# TinyFET.net
KiCad netlist of a schematic drawn in EAGLE
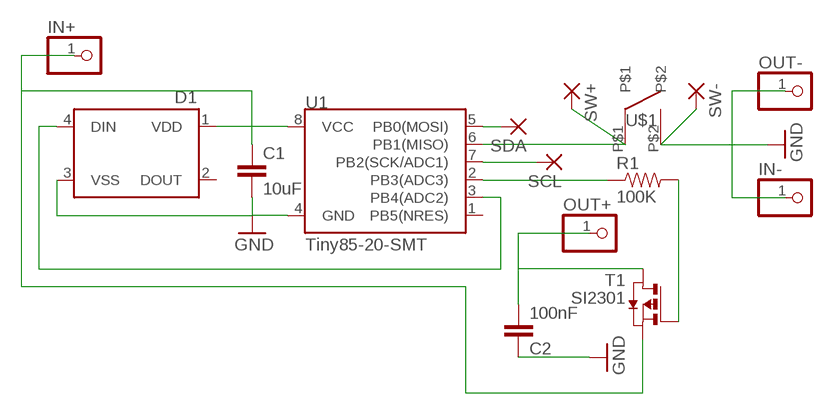
[diagram p0: schematic, sheet 1]

(export (version "E")
  (design (tool "Eeschema 10.0.6"))
  (components
    (comp (ref "C1")
      (value "10uF")
      (footprint "eagle-import:C0603K")
      (libsource (lib "eagle-import") (part "resistor_C-EUC0603K"))
    )
    (comp (ref "C2")
      (value "100nF")
      (footprint "eagle-import:C0603K")
      (libsource (lib "eagle-import") (part "C-EUC0603K"))
    )
    (comp (ref "D1")
      (value "WS2812B")
      (footprint "eagle-import:WS2812B")
      (libsource (lib "eagle-import") (part "WS2812B"))
    )
    (comp (ref "IN+")
      (value "PINHD-1X1")
      (footprint "eagle-import:1X01")
      (libsource (lib "eagle-import") (part "PINHD-1X1"))
    )
    (comp (ref "IN-")
      (value "PINHD-1X1")
      (footprint "eagle-import:1X01")
      (libsource (lib "eagle-import") (part "PINHD-1X1"))
    )
    (comp (ref "OUT+")
      (value "PINHD-1X1")
      (footprint "eagle-import:1X01")
      (libsource (lib "eagle-import") (part "PINHD-1X1"))
    )
    (comp (ref "OUT-")
      (value "PINHD-1X1")
      (footprint "eagle-import:1X01")
      (libsource (lib "eagle-import") (part "PINHD-1X1"))
    )
    (comp (ref "R1")
      (value "100K")
      (footprint "eagle-import:0603-RES")
      (libsource (lib "eagle-import") (part "RESISTOR0603-RES"))
    )
    (comp (ref "SCL")
      (value "SMD2")
      (footprint "eagle-import:SMD1,27-2,54")
      (libsource (lib "eagle-import") (part "SMD2"))
    )
    (comp (ref "SDA")
      (value "SMD2")
      (footprint "eagle-import:SMD1,27-2,54")
      (libsource (lib "eagle-import") (part "SMD2"))
    )
    (comp (ref "SW+")
      (value "SMD2")
      (footprint "eagle-import:SMD1,27-2,54")
      (libsource (lib "eagle-import") (part "SMD2"))
    )
    (comp (ref "SW-")
      (value "SMD2")
      (footprint "eagle-import:SMD1,27-2,54")
      (libsource (lib "eagle-import") (part "SMD2"))
    )
    (comp (ref "T1")
      (value "SI2301")
      (footprint "eagle-import:SOT-23")
      (libsource (lib "eagle-import") (part "PMOSSOT23"))
    )
    (comp (ref "U$1")
      (value "5MMSNAP")
      (footprint "eagle-import:5MMSNAP")
      (libsource (lib "eagle-import") (part "5MMSNAP"))
    )
    (comp (ref "U1")
      (value "Tiny85-20-SMT")
      (footprint "eagle-import:SO08-EIAJ")
      (libsource (lib "eagle-import") (part "ATTINY45TINY85-20-SMT"))
    )
  )
  (nets
    (net (code "1") (name "GND") (class "Default")
      (node (ref "C1") (pin "2") (pinfunction "2_2") (pintype "passive"))
      (node (ref "C2") (pin "1") (pinfunction "1_1") (pintype "passive"))
      (node (ref "D1") (pin "3") (pinfunction "VSS_3") (pintype "power_in"))
      (node (ref "IN-") (pin "1") (pinfunction "1_1") (pintype "passive"))
      (node (ref "OUT-") (pin "1") (pinfunction "1_1") (pintype "passive"))
      (node (ref "SW-") (pin "1") (pinfunction "P_1") (pintype "passive"))
      (node (ref "U$1") (pin "P$2") (pinfunction "P$2_P$2") (pintype "bidirectional"))
      (node (ref "U1") (pin "4") (pinfunction "GND_4") (pintype "bidirectional"))
    )
    (net (code "2") (name "Net-(D1-DIN)") (class "Default")
      (node (ref "D1") (pin "4") (pinfunction "DIN_4") (pintype "input"))
      (node (ref "U1") (pin "3") (pinfunction "PB4(ADC2)_3") (pintype "bidirectional"))
    )
    (net (code "3") (name "Net-(D1-VDD)") (class "Default")
      (node (ref "C1") (pin "1") (pinfunction "1_1") (pintype "passive"))
      (node (ref "D1") (pin "1") (pinfunction "VDD_1") (pintype "power_in"))
      (node (ref "IN+") (pin "1") (pinfunction "1_1") (pintype "passive"))
      (node (ref "T1") (pin "2") (pinfunction "S_2") (pintype "passive"))
      (node (ref "U1") (pin "8") (pinfunction "VCC_8") (pintype "bidirectional"))
    )
    (net (code "4") (name "Net-(SCL-P)") (class "Default")
      (node (ref "SCL") (pin "1") (pinfunction "P_1") (pintype "passive"))
      (node (ref "U1") (pin "7") (pinfunction "PB2(SCK/ADC1)_7") (pintype "bidirectional"))
    )
    (net (code "5") (name "Net-(SDA-P)") (class "Default")
      (node (ref "SDA") (pin "1") (pinfunction "P_1") (pintype "passive"))
      (node (ref "U1") (pin "5") (pinfunction "PB0(MOSI)_5") (pintype "bidirectional"))
    )
    (net (code "6") (name "Net-(SW+-P)") (class "Default")
      (node (ref "SW+") (pin "1") (pinfunction "P_1") (pintype "passive"))
      (node (ref "U$1") (pin "P$1") (pinfunction "P$1_P$1") (pintype "bidirectional"))
      (node (ref "U1") (pin "6") (pinfunction "PB1(MISO)_6") (pintype "bidirectional"))
    )
    (net (code "7") (name "Net-(T1-D)") (class "Default")
      (node (ref "C2") (pin "2") (pinfunction "2_2") (pintype "passive"))
      (node (ref "OUT+") (pin "1") (pinfunction "1_1") (pintype "passive"))
      (node (ref "T1") (pin "1") (pinfunction "D_1") (pintype "passive"))
    )
    (net (code "8") (name "Net-(T1-G)") (class "Default")
      (node (ref "R1") (pin "2") (pinfunction "2_2") (pintype "passive"))
      (node (ref "T1") (pin "3") (pinfunction "G_3") (pintype "passive"))
    )
    (net (code "9") (name "Net-(U1-PB3(ADC3))") (class "Default")
      (node (ref "R1") (pin "1") (pinfunction "1_1") (pintype "passive"))
      (node (ref "U1") (pin "2") (pinfunction "PB3(ADC3)_2") (pintype "bidirectional"))
    )
    (net (code "10") (name "unconnected-(D1-DOUT-Pad2)") (class "Default")
      (node (ref "D1") (pin "2") (pinfunction "DOUT_2") (pintype "output"))
    )
    (net (code "11") (name "unconnected-(U1-PB5(NRES)-Pad1)") (class "Default")
      (node (ref "U1") (pin "1") (pinfunction "PB5(NRES)_1") (pintype "bidirectional"))
    )
  )
)
